# usbB_isp.net
KiCad netlist of a schematic drawn in EAGLE
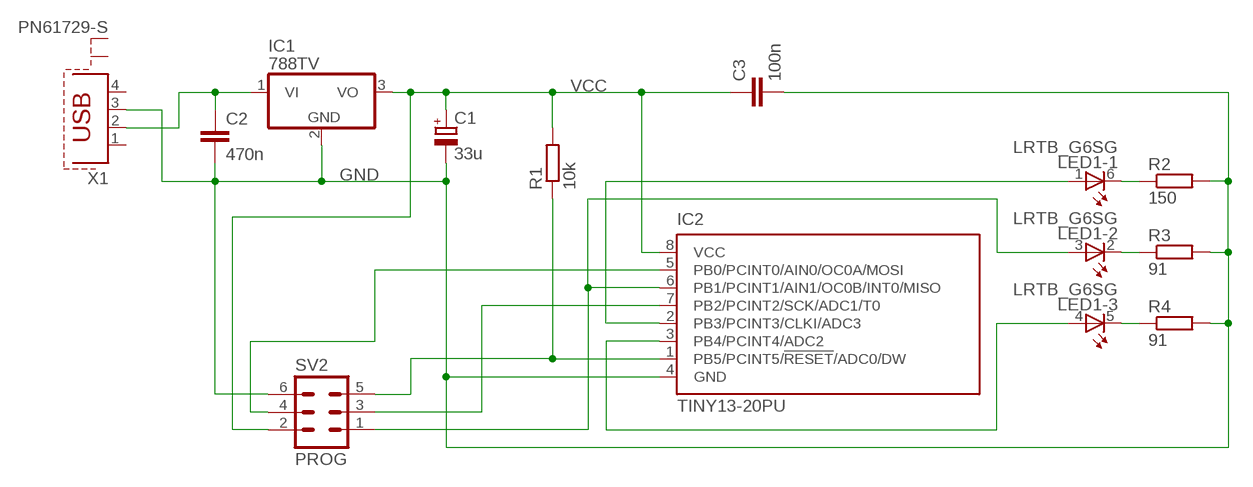
[diagram p0: schematic, sheet 1]

(export (version "E")
  (design (tool "Eeschema 10.0.6"))
  (components
    (comp (ref "C1")
      (value "33u")
      (footprint "eagle-import:E2,5-6E")
      (libsource (lib "eagle-import") (part "CPOL-EUE2,5-6E"))
    )
    (comp (ref "C2")
      (value "470n")
      (footprint "eagle-import:C050-025X075")
      (libsource (lib "eagle-import") (part "C-EU050-025X075"))
    )
    (comp (ref "C3")
      (value "100n")
      (footprint "eagle-import:C050-025X075")
      (libsource (lib "eagle-import") (part "C-EU050-025X075"))
    )
    (comp (ref "IC1")
      (value "788TV")
      (footprint "eagle-import:TO220V")
      (libsource (lib "eagle-import") (part "78TV8"))
    )
    (comp (ref "IC2")
      (value "TINY13-20PU")
      (footprint "eagle-import:DIL08")
      (fields (field (name "MPN") "ATTINY13-20PU"))
      (libsource (lib "eagle-import") (part "TINY13PU-20"))
    )
    (comp (ref "LED1")
      (value "LRTB_G6SG")
      (footprint "eagle-import:LRTB_G6SG")
      (libsource (lib "eagle-import") (part "LRTB_G6SG"))
    )
    (comp (ref "R1")
      (value "10k")
      (footprint "eagle-import:0204_7")
      (libsource (lib "eagle-import") (part "R-EU_0204/7"))
    )
    (comp (ref "R2")
      (value "150")
      (footprint "eagle-import:0204_7")
      (libsource (lib "eagle-import") (part "R-EU_0204/7"))
    )
    (comp (ref "R3")
      (value "91")
      (footprint "eagle-import:0204_7")
      (libsource (lib "eagle-import") (part "R-EU_0204/7"))
    )
    (comp (ref "R4")
      (value "91")
      (footprint "eagle-import:0204_7")
      (libsource (lib "eagle-import") (part "R-EU_0204/7"))
    )
    (comp (ref "SV2")
      (value "PROG")
      (footprint "eagle-import:ML6")
      (libsource (lib "eagle-import") (part "ML6"))
    )
    (comp (ref "X1")
      (value "PN61729-S")
      (footprint "eagle-import:PN61729-S")
      (libsource (lib "eagle-import") (part "PN61729-S"))
    )
  )
  (nets
    (net (code "1") (name "/GND") (class "Default")
      (node (ref "C1") (pin "-") (pinfunction "-_-") (pintype "passive"))
      (node (ref "C2") (pin "2") (pinfunction "2_2") (pintype "passive"))
      (node (ref "C3") (pin "2") (pinfunction "2_2") (pintype "passive"))
      (node (ref "IC1") (pin "2") (pinfunction "GND_2") (pintype "passive"))
      (node (ref "IC2") (pin "4") (pinfunction "GND_4") (pintype "power_in"))
      (node (ref "R2") (pin "2") (pinfunction "2_2") (pintype "passive"))
      (node (ref "R3") (pin "2") (pinfunction "2_2") (pintype "passive"))
      (node (ref "R4") (pin "2") (pinfunction "2_2") (pintype "passive"))
      (node (ref "SV2") (pin "6") (pinfunction "6_6") (pintype "passive"))
      (node (ref "X1") (pin "3") (pinfunction "3_3") (pintype "passive"))
    )
    (net (code "2") (name "/VCC") (class "Default")
      (node (ref "C1") (pin "+") (pinfunction "+_+") (pintype "passive"))
      (node (ref "C3") (pin "1") (pinfunction "1_1") (pintype "passive"))
      (node (ref "IC1") (pin "3") (pinfunction "VO_3") (pintype "passive"))
      (node (ref "IC2") (pin "8") (pinfunction "VCC_8") (pintype "power_in"))
      (node (ref "R1") (pin "2") (pinfunction "2_2") (pintype "passive"))
      (node (ref "SV2") (pin "2") (pinfunction "2_2") (pintype "passive"))
    )
    (net (code "3") (name "Net-(IC1-VI)") (class "Default")
      (node (ref "C2") (pin "1") (pinfunction "1_1") (pintype "passive"))
      (node (ref "IC1") (pin "1") (pinfunction "VI_1") (pintype "input"))
      (node (ref "X1") (pin "2") (pinfunction "2_2") (pintype "passive"))
    )
    (net (code "4") (name "Net-(IC2-PB0{slash}PCINT0{slash}AIN0{slash}OC0A{slash}MOSI)") (class "Default")
      (node (ref "IC2") (pin "5") (pinfunction "PB0/PCINT0/AIN0/OC0A/MOSI_5") (pintype "bidirectional"))
      (node (ref "SV2") (pin "4") (pinfunction "4_4") (pintype "passive"))
    )
    (net (code "5") (name "Net-(IC2-PB1{slash}PCINT1{slash}AIN1{slash}OC0B{slash}INT0{slash}MISO)") (class "Default")
      (node (ref "IC2") (pin "6") (pinfunction "PB1/PCINT1/AIN1/OC0B/INT0/MISO_6") (pintype "bidirectional"))
      (node (ref "LED1") (pin "3") (pinfunction "A_3") (pintype "passive"))
      (node (ref "SV2") (pin "1") (pinfunction "1_1") (pintype "passive"))
    )
    (net (code "6") (name "Net-(IC2-PB2{slash}PCINT2{slash}SCK{slash}ADC1{slash}T0)") (class "Default")
      (node (ref "IC2") (pin "7") (pinfunction "PB2/PCINT2/SCK/ADC1/T0_7") (pintype "bidirectional"))
      (node (ref "SV2") (pin "3") (pinfunction "3_3") (pintype "passive"))
    )
    (net (code "7") (name "Net-(IC2-PB3{slash}PCINT3{slash}CLKI{slash}ADC3)") (class "Default")
      (node (ref "IC2") (pin "2") (pinfunction "PB3/PCINT3/CLKI/ADC3_2") (pintype "bidirectional"))
      (node (ref "LED1") (pin "1") (pinfunction "A_1") (pintype "passive"))
    )
    (net (code "8") (name "Net-(IC2-PB4{slash}PCINT4{slash}ADC2)") (class "Default")
      (node (ref "IC2") (pin "3") (pinfunction "PB4/PCINT4/ADC2_3") (pintype "bidirectional"))
      (node (ref "LED1") (pin "4") (pinfunction "A_4") (pintype "passive"))
    )
    (net (code "9") (name "Net-(IC2-PB5{slash}PCINT5{slash}~{RESET}{slash}ADC0{slash}DW)") (class "Default")
      (node (ref "IC2") (pin "1") (pinfunction "PB5/PCINT5/~{RESET}/ADC0/DW_1") (pintype "bidirectional"))
      (node (ref "R1") (pin "1") (pinfunction "1_1") (pintype "passive"))
      (node (ref "SV2") (pin "5") (pinfunction "5_5") (pintype "passive"))
    )
    (net (code "10") (name "Net-(LED1A-C)") (class "Default")
      (node (ref "LED1") (pin "6") (pinfunction "C_6") (pintype "passive"))
      (node (ref "R2") (pin "1") (pinfunction "1_1") (pintype "passive"))
    )
    (net (code "11") (name "Net-(LED1B-C)") (class "Default")
      (node (ref "LED1") (pin "2") (pinfunction "C_2") (pintype "passive"))
      (node (ref "R3") (pin "1") (pinfunction "1_1") (pintype "passive"))
    )
    (net (code "12") (name "Net-(LED1C-C)") (class "Default")
      (node (ref "LED1") (pin "5") (pinfunction "C_5") (pintype "passive"))
      (node (ref "R4") (pin "1") (pinfunction "1_1") (pintype "passive"))
    )
    (net (code "13") (name "unconnected-(X1-Pad1)") (class "Default")
      (node (ref "X1") (pin "1") (pinfunction "1_1") (pintype "passive"))
    )
    (net (code "14") (name "unconnected-(X1-Pad4)") (class "Default")
      (node (ref "X1") (pin "4") (pinfunction "4_4") (pintype "passive"))
    )
    (net (code "15") (name "unconnected-(X1-PadS1)") (class "Default")
      (node (ref "X1") (pin "S1") (pinfunction "S1_S1") (pintype "passive"))
    )
    (net (code "16") (name "unconnected-(X1-PadS2)") (class "Default")
      (node (ref "X1") (pin "S2") (pinfunction "S2_S2") (pintype "passive"))
    )
  )
)
